# SCH_5730_LED_array_with_switch_2022-07-2.net
KiCad netlist of a schematic drawn in EasyEDA
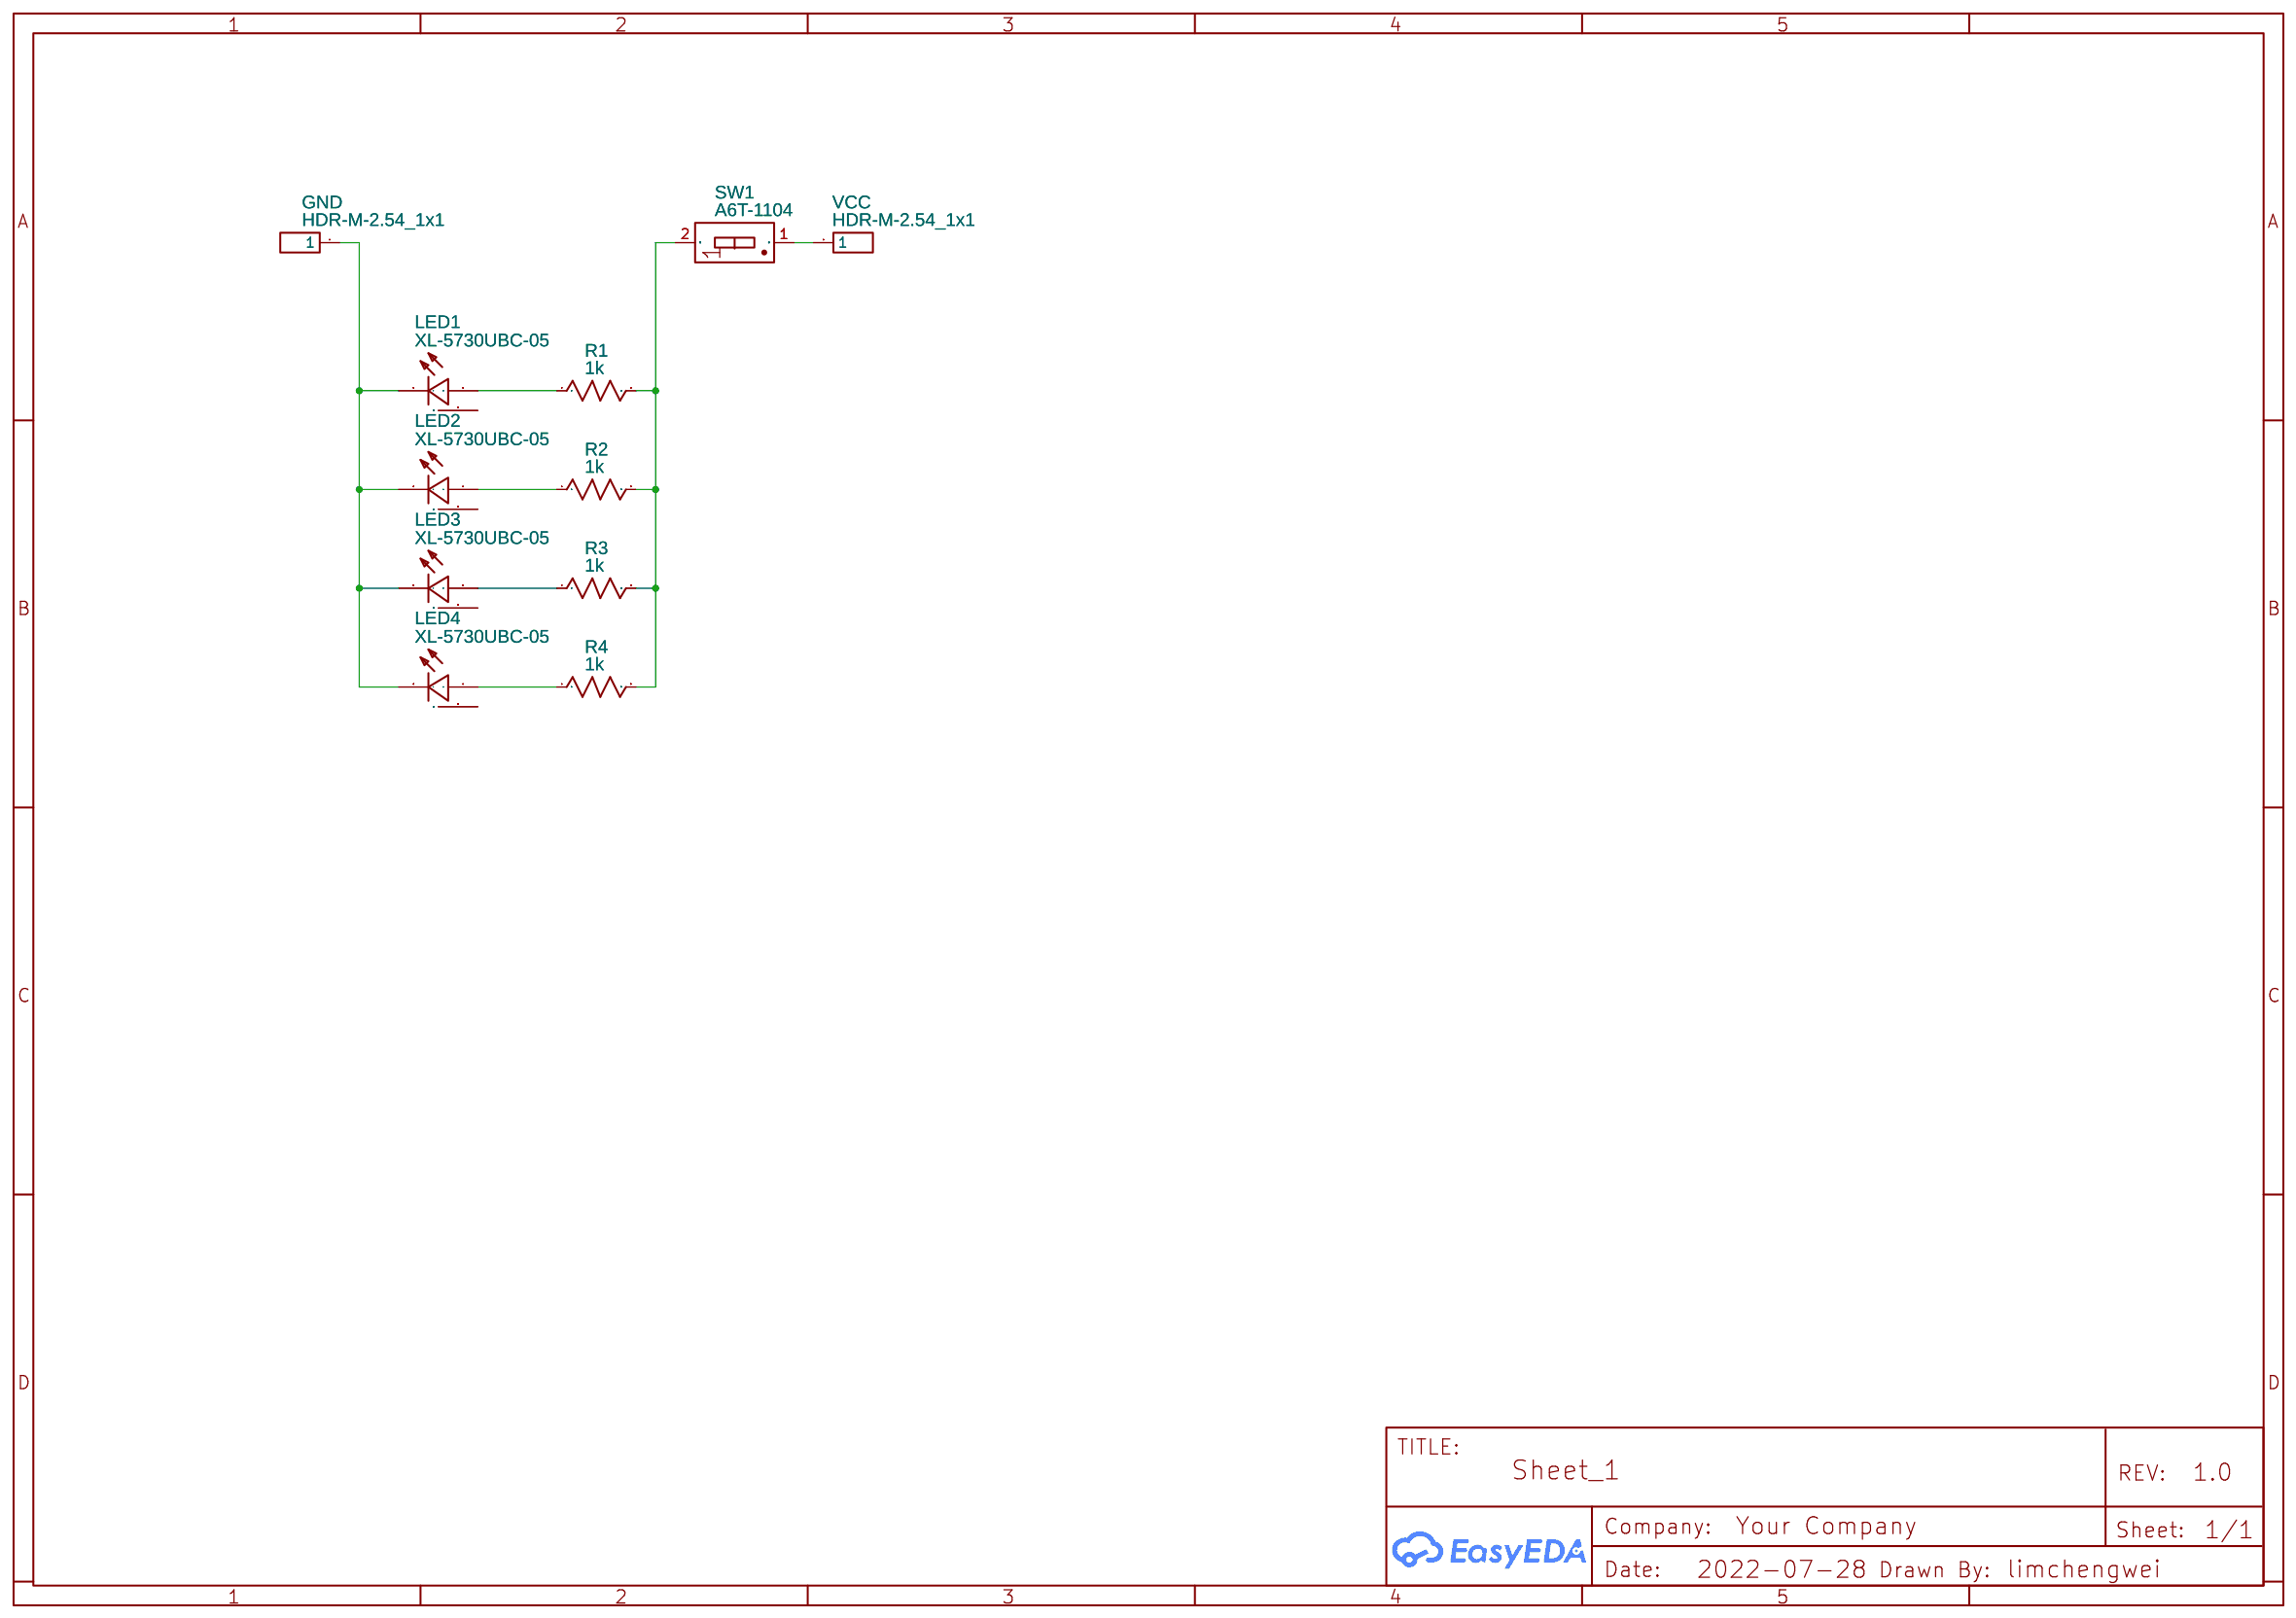
[diagram p0: schematic sheet]

(export (version "E")
  (design (tool "Eeschema 10.0.6"))
  (components
    (comp (ref "GND")
      (value "HDR-M-2.54_1x1")
      (fields (field (name "BOM_Supplier Part") "C81276"))
      (libsource (lib "") (part "HDR-M-2.54_1x1"))
    )
    (comp (ref "LED1")
      (value "XL-5730UBC-05")
      (fields (field (name "BOM_Supplier Part") "C2843885"))
      (libsource (lib "") (part "XL-5730UBC-05"))
    )
    (comp (ref "LED2")
      (value "XL-5730UBC-05")
      (fields (field (name "BOM_Supplier Part") "C2843885"))
      (libsource (lib "") (part "XL-5730UBC-05"))
    )
    (comp (ref "LED3")
      (value "XL-5730UBC-05")
      (fields (field (name "BOM_Supplier Part") "C2843885"))
      (libsource (lib "") (part "XL-5730UBC-05"))
    )
    (comp (ref "LED4")
      (value "XL-5730UBC-05")
      (fields (field (name "BOM_Supplier Part") "C2843885"))
      (libsource (lib "") (part "XL-5730UBC-05"))
    )
    (comp (ref "R1") (value "1k") (libsource (lib "") (part "R_1812_US")))
    (comp (ref "R2") (value "1k") (libsource (lib "") (part "R_1812_US")))
    (comp (ref "R3") (value "1k") (libsource (lib "") (part "R_1812_US")))
    (comp (ref "R4") (value "1k") (libsource (lib "") (part "R_1812_US")))
    (comp (ref "SW1")
      (value "A6T-1104")
      (fields (field (name "BOM_Supplier Part") "C306874"))
      (libsource (lib "") (part "A6T-1104"))
    )
    (comp (ref "VCC")
      (value "HDR-M-2.54_1x1")
      (fields (field (name "BOM_Supplier Part") "C81276"))
      (libsource (lib "") (part "HDR-M-2.54_1x1_1"))
    )
  )
  (nets
    (net (code "1") (name "Net-(LED1-+)") (class "Default")
      (node (ref "LED1") (pin "1") (pinfunction "+_1") (pintype "unspecified"))
      (node (ref "R1") (pin "1") (pinfunction "1_1") (pintype "unspecified"))
    )
    (net (code "2") (name "Net-(LED1--)") (class "Default")
      (node (ref "GND") (pin "1") (pinfunction "1_1") (pintype "input"))
      (node (ref "LED1") (pin "2") (pinfunction "-_2") (pintype "unspecified"))
      (node (ref "LED2") (pin "2") (pinfunction "-_2") (pintype "unspecified"))
      (node (ref "LED3") (pin "2") (pinfunction "-_2") (pintype "unspecified"))
      (node (ref "LED4") (pin "2") (pinfunction "-_2") (pintype "unspecified"))
    )
    (net (code "3") (name "Net-(LED2-+)") (class "Default")
      (node (ref "LED2") (pin "1") (pinfunction "+_1") (pintype "unspecified"))
      (node (ref "R2") (pin "1") (pinfunction "1_1") (pintype "unspecified"))
    )
    (net (code "4") (name "Net-(LED3-+)") (class "Default")
      (node (ref "LED3") (pin "1") (pinfunction "+_1") (pintype "unspecified"))
      (node (ref "R3") (pin "1") (pinfunction "1_1") (pintype "unspecified"))
    )
    (net (code "5") (name "Net-(LED4-+)") (class "Default")
      (node (ref "LED4") (pin "1") (pinfunction "+_1") (pintype "unspecified"))
      (node (ref "R4") (pin "1") (pinfunction "1_1") (pintype "unspecified"))
    )
    (net (code "6") (name "Net-(SW1-PIN1)") (class "Default")
      (node (ref "SW1") (pin "1") (pinfunction "PIN1_1") (pintype "unspecified"))
      (node (ref "VCC") (pin "1") (pinfunction "1_1") (pintype "input"))
    )
    (net (code "7") (name "Net-(SW1-PIN2)") (class "Default")
      (node (ref "R1") (pin "2") (pinfunction "2_2") (pintype "unspecified"))
      (node (ref "R2") (pin "2") (pinfunction "2_2") (pintype "unspecified"))
      (node (ref "R3") (pin "2") (pinfunction "2_2") (pintype "unspecified"))
      (node (ref "R4") (pin "2") (pinfunction "2_2") (pintype "unspecified"))
      (node (ref "SW1") (pin "2") (pinfunction "PIN2_2") (pintype "unspecified"))
    )
    (net (code "8") (name "unconnected-(LED1-Pad3)") (class "Default")
      (node (ref "LED1") (pin "3") (pinfunction "3_3") (pintype "unspecified"))
    )
    (net (code "9") (name "unconnected-(LED2-Pad3)") (class "Default")
      (node (ref "LED2") (pin "3") (pinfunction "3_3") (pintype "unspecified"))
    )
    (net (code "10") (name "unconnected-(LED3-Pad3)") (class "Default")
      (node (ref "LED3") (pin "3") (pinfunction "3_3") (pintype "unspecified"))
    )
    (net (code "11") (name "unconnected-(LED4-Pad3)") (class "Default")
      (node (ref "LED4") (pin "3") (pinfunction "3_3") (pintype "unspecified"))
    )
  )
)
